# Hifi_Nutube_DAC.net
KiCad netlist of a schematic drawn in EAGLE
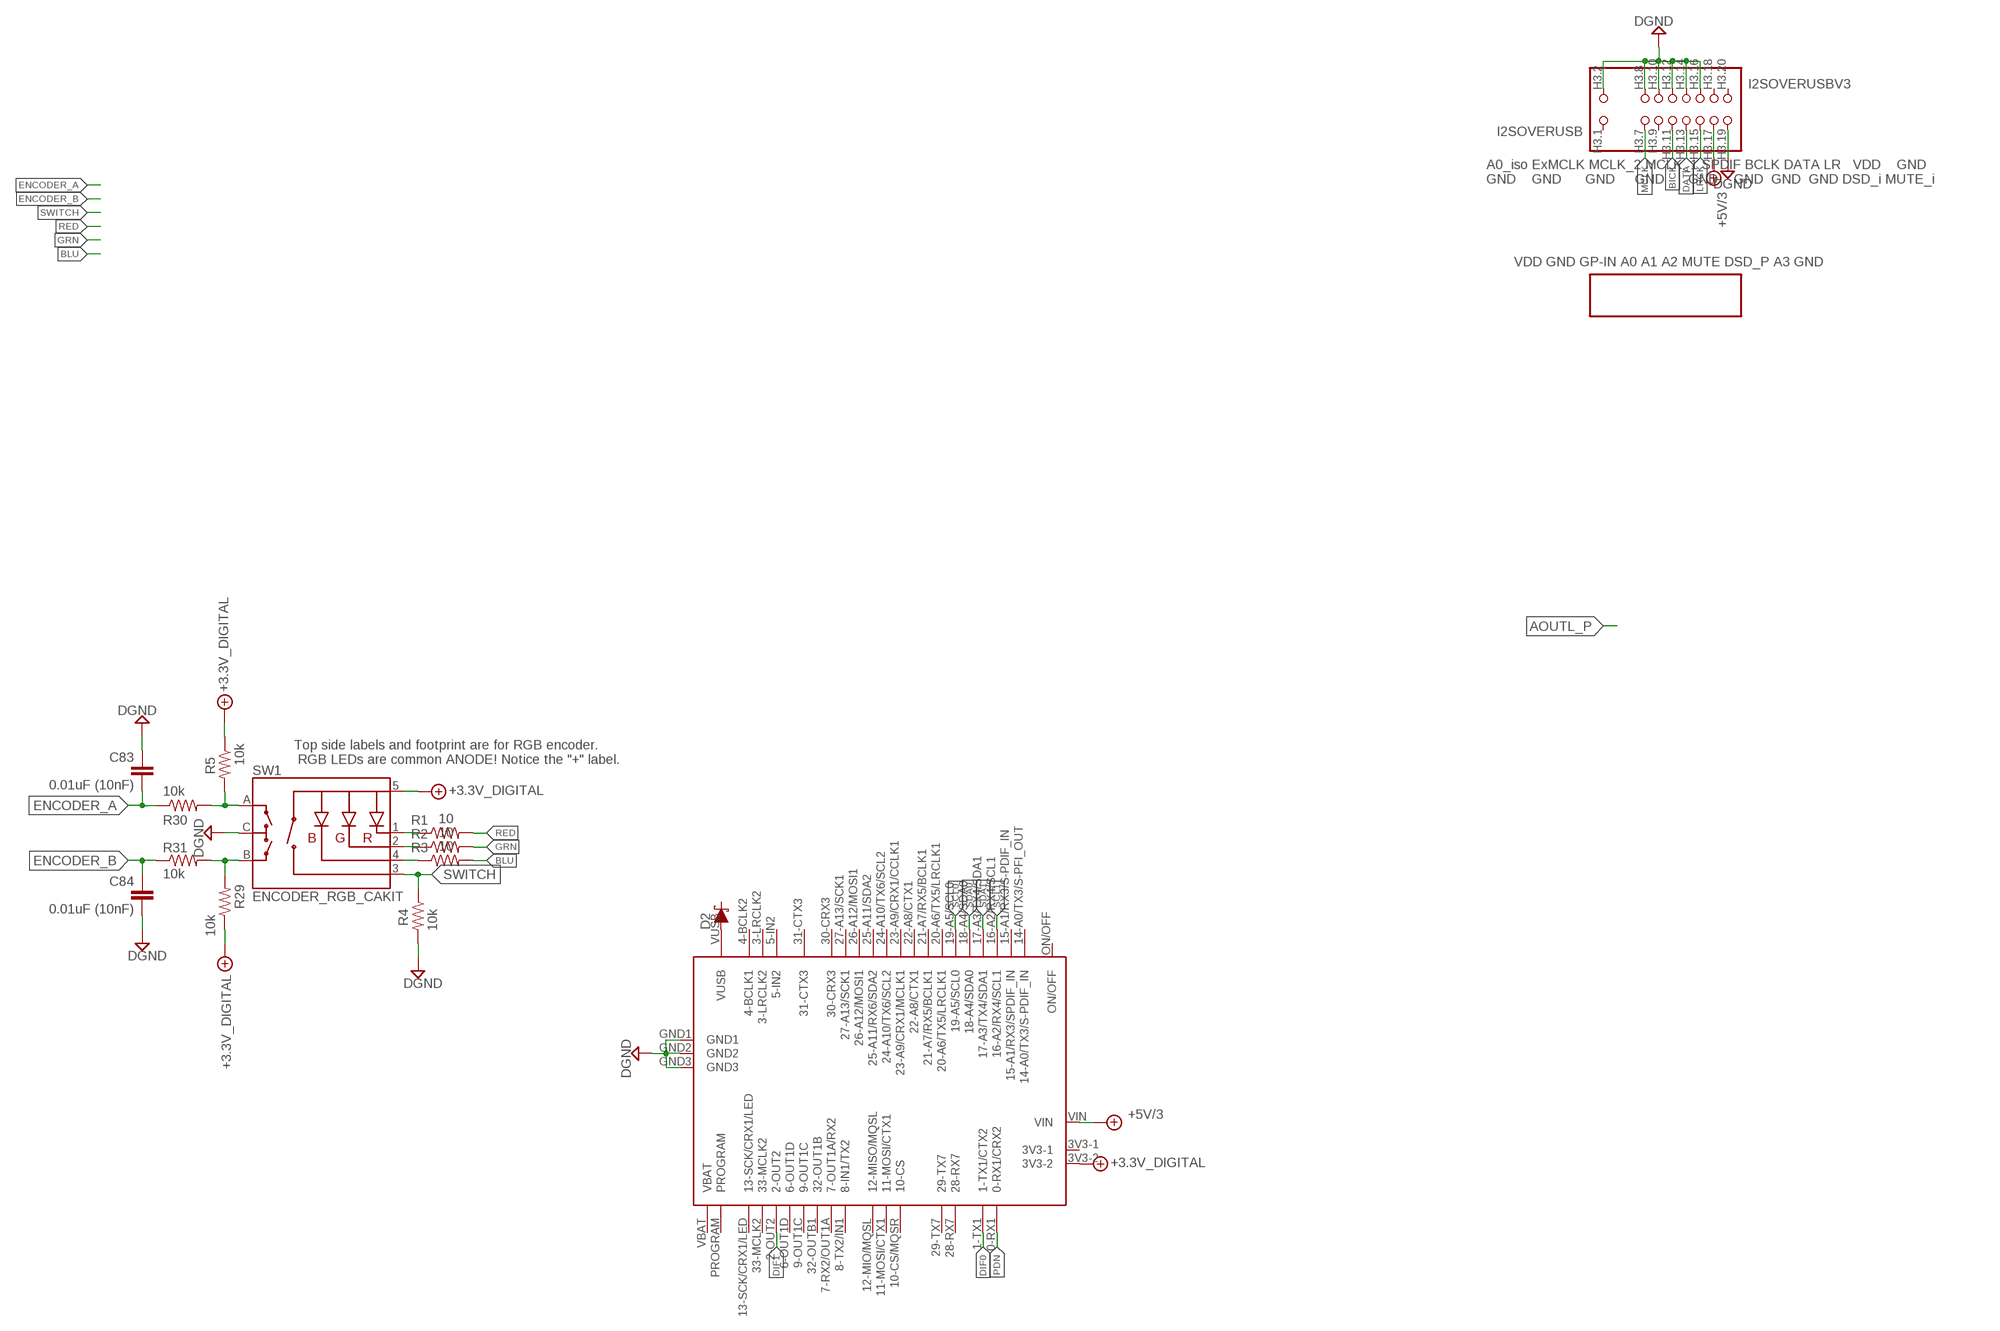
[diagram p0: schematic, sheet 1]

(export (version "E")
  (design (tool "Eeschema 10.0.6"))
  (components
    (comp (ref "C83")
      (value "0.01uF (10nF)")
      (footprint "eagle-import:C0603")
      (fields
        (field (name "DISTRIBUTOR_PART_NUMBER") "710-885012206014")
        (field (name "MANUFACTURER_PART_NUMBER") "885012206014")
      )
      (libsource (lib "eagle-import") (part "C__0603885012206014"))
    )
    (comp (ref "C84")
      (value "0.01uF (10nF)")
      (footprint "eagle-import:C0603")
      (fields
        (field (name "DISTRIBUTOR_PART_NUMBER") "710-885012206014")
        (field (name "MANUFACTURER_PART_NUMBER") "885012206014")
      )
      (libsource (lib "eagle-import") (part "C__0603885012206014"))
    )
    (comp (ref "D2")
      (value "SS14-DIODE-SCHOTTKY-SS14")
      (footprint "eagle-import:SMA-DIODE")
      (fields
        (field (name "DISTRIBUTOR_PART_NUMBER") "241-SS14_R1_00001")
        (field (name "MANUFACTURER_PART_NUMBER") "SS14_R1_00001")
      )
      (libsource (lib "eagle-import") (part "SS14-DIODE-SCHOTTKY-SS14"))
    )
    (comp (ref "I2SOVERUSB")
      (value "I2SOVERUSBV3")
      (footprint "eagle-import:I2SOVERUSBV3")
      (libsource (lib "eagle-import") (part "I2SOVERUSBV3"))
    )
    (comp (ref "R1")
      (value "10")
      (footprint "eagle-import:R0603")
      (fields
        (field (name "DISTRIBUTOR_PART_NUMBER") "603-RC0603FR-7W10RL")
        (field (name "MANUFACTURER_PART_NUMBER") "RC0603FR-7W10RL")
      )
      (libsource (lib "eagle-import") (part "R__0603RC0603FR-7W10RL"))
    )
    (comp (ref "R2")
      (value "10")
      (footprint "eagle-import:R0603")
      (fields
        (field (name "DISTRIBUTOR_PART_NUMBER") "603-RC0603FR-7W10RL")
        (field (name "MANUFACTURER_PART_NUMBER") "RC0603FR-7W10RL")
      )
      (libsource (lib "eagle-import") (part "R__0603RC0603FR-7W10RL"))
    )
    (comp (ref "R3")
      (value "10")
      (footprint "eagle-import:R0603")
      (fields
        (field (name "DISTRIBUTOR_PART_NUMBER") "603-RC0603FR-7W10RL")
        (field (name "MANUFACTURER_PART_NUMBER") "RC0603FR-7W10RL")
      )
      (libsource (lib "eagle-import") (part "R__0603RC0603FR-7W10RL"))
    )
    (comp (ref "R4")
      (value "10k")
      (footprint "eagle-import:R0603")
      (fields
        (field (name "DISTRIBUTOR_PART_NUMBER") "652-CMP0603AFX-1002L")
        (field (name "MANUFACTURER_PART_NUMBER") "CMP0603AFX-1002ELF")
      )
      (libsource (lib "eagle-import") (part "R__0603CMP0603AFX-1002ELF"))
    )
    (comp (ref "R5")
      (value "10k")
      (footprint "eagle-import:R0603")
      (fields
        (field (name "DISTRIBUTOR_PART_NUMBER") "652-CMP0603AFX-1002L")
        (field (name "MANUFACTURER_PART_NUMBER") "CMP0603AFX-1002ELF")
      )
      (libsource (lib "eagle-import") (part "R__0603CMP0603AFX-1002ELF"))
    )
    (comp (ref "R29")
      (value "10k")
      (footprint "eagle-import:R0603")
      (fields
        (field (name "DISTRIBUTOR_PART_NUMBER") "652-CMP0603AFX-1002L")
        (field (name "MANUFACTURER_PART_NUMBER") "CMP0603AFX-1002ELF")
      )
      (libsource (lib "eagle-import") (part "R__0603CMP0603AFX-1002ELF"))
    )
    (comp (ref "R30")
      (value "10k")
      (footprint "eagle-import:R0603")
      (fields
        (field (name "DISTRIBUTOR_PART_NUMBER") "652-CMP0603AFX-1002L")
        (field (name "MANUFACTURER_PART_NUMBER") "CMP0603AFX-1002ELF")
      )
      (libsource (lib "eagle-import") (part "R__0603CMP0603AFX-1002ELF"))
    )
    (comp (ref "R31")
      (value "10k")
      (footprint "eagle-import:R0603")
      (fields
        (field (name "DISTRIBUTOR_PART_NUMBER") "652-CMP0603AFX-1002L")
        (field (name "MANUFACTURER_PART_NUMBER") "CMP0603AFX-1002ELF")
      )
      (libsource (lib "eagle-import") (part "R__0603CMP0603AFX-1002ELF"))
    )
    (comp (ref "SW1")
      (value "ENCODER_RGB_CAKIT")
      (footprint "eagle-import:ENCODER_LED_3_KIT")
      (libsource (lib "eagle-import") (part "ENCODER_RGB_CAKIT"))
    )
    (comp (ref "U$4")
      (value "TEENSY40")
      (footprint "eagle-import:TEENSY40")
      (libsource (lib "eagle-import") (part "TEENSY40"))
    )
  )
  (nets
    (net (code "1") (name "+3.3V_DIGITAL") (class "Default")
      (node (ref "R29") (pin "1") (pinfunction "1_1") (pintype "passive"))
      (node (ref "R5") (pin "1") (pinfunction "1_1") (pintype "passive"))
      (node (ref "SW1") (pin "5") (pinfunction "+_5") (pintype "passive"))
      (node (ref "U$4") (pin "3V3-2") (pinfunction "3V3-2_3V3-2") (pintype "bidirectional"))
    )
    (net (code "2") (name "+5V{slash}3") (class "Default")
      (node (ref "I2SOVERUSB") (pin "H3.17") (pinfunction "H3.17_H3.17") (pintype "passive"))
      (node (ref "U$4") (pin "VIN") (pinfunction "VIN_VIN") (pintype "bidirectional"))
    )
    (net (code "4") (name "BICK") (class "Default")
      (node (ref "I2SOVERUSB") (pin "H3.11") (pinfunction "H3.11_H3.11") (pintype "passive"))
    )
    (net (code "5") (name "BLU") (class "Default")
      (node (ref "R3") (pin "2") (pinfunction "2_2") (pintype "passive"))
    )
    (net (code "6") (name "DATA") (class "Default")
      (node (ref "I2SOVERUSB") (pin "H3.13") (pinfunction "H3.13_H3.13") (pintype "passive"))
    )
    (net (code "7") (name "DGND") (class "Default")
      (node (ref "C83") (pin "1") (pinfunction "1_1") (pintype "passive"))
      (node (ref "C84") (pin "2") (pinfunction "2_2") (pintype "passive"))
      (node (ref "I2SOVERUSB") (pin "H3.10") (pinfunction "H3.10_H3.10") (pintype "passive"))
      (node (ref "I2SOVERUSB") (pin "H3.12") (pinfunction "H3.12_H3.12") (pintype "passive"))
      (node (ref "I2SOVERUSB") (pin "H3.14") (pinfunction "H3.14_H3.14") (pintype "passive"))
      (node (ref "I2SOVERUSB") (pin "H3.16") (pinfunction "H3.16_H3.16") (pintype "passive"))
      (node (ref "I2SOVERUSB") (pin "H3.19") (pinfunction "H3.19_H3.19") (pintype "passive"))
      (node (ref "I2SOVERUSB") (pin "H3.2") (pinfunction "H3.2_H3.2") (pintype "passive"))
      (node (ref "I2SOVERUSB") (pin "H3.8") (pinfunction "H3.8_H3.8") (pintype "passive"))
      (node (ref "R4") (pin "2") (pinfunction "2_2") (pintype "passive"))
      (node (ref "SW1") (pin "C") (pinfunction "C_C") (pintype "bidirectional"))
      (node (ref "U$4") (pin "GND1") (pinfunction "GND1_GND1") (pintype "bidirectional"))
      (node (ref "U$4") (pin "GND2") (pinfunction "GND2_GND2") (pintype "bidirectional"))
      (node (ref "U$4") (pin "GND3") (pinfunction "GND3_GND3") (pintype "bidirectional"))
    )
    (net (code "8") (name "DIF0") (class "Default")
      (node (ref "U$4") (pin "1-TX1") (pinfunction "1-TX1/CTX2_1-TX1") (pintype "bidirectional"))
    )
    (net (code "9") (name "DIF1") (class "Default")
      (node (ref "U$4") (pin "2-OUT2") (pinfunction "2-OUT2_2-OUT2") (pintype "bidirectional"))
    )
    (net (code "10") (name "ENCODER_A") (class "Default")
      (node (ref "C83") (pin "2") (pinfunction "2_2") (pintype "passive"))
      (node (ref "R30") (pin "1") (pinfunction "1_1") (pintype "passive"))
    )
    (net (code "11") (name "ENCODER_B") (class "Default")
      (node (ref "C84") (pin "1") (pinfunction "1_1") (pintype "passive"))
      (node (ref "R31") (pin "1") (pinfunction "1_1") (pintype "passive"))
    )
    (net (code "12") (name "GRN") (class "Default")
      (node (ref "R2") (pin "2") (pinfunction "2_2") (pintype "passive"))
    )
    (net (code "13") (name "LRCK") (class "Default")
      (node (ref "I2SOVERUSB") (pin "H3.15") (pinfunction "H3.15_H3.15") (pintype "passive"))
    )
    (net (code "14") (name "MCLK") (class "Default")
      (node (ref "I2SOVERUSB") (pin "H3.7") (pinfunction "H3.7_H3.7") (pintype "passive"))
    )
    (net (code "15") (name "Net-(D2-PadA)") (class "Default")
      (node (ref "D2") (pin "A") (pinfunction "A_A") (pintype "passive"))
      (node (ref "U$4") (pin "VUSB") (pinfunction "VUSB_VUSB") (pintype "bidirectional"))
    )
    (net (code "16") (name "Net-(R29-Pad2)") (class "Default")
      (node (ref "R29") (pin "2") (pinfunction "2_2") (pintype "passive"))
      (node (ref "R31") (pin "2") (pinfunction "2_2") (pintype "passive"))
      (node (ref "SW1") (pin "B") (pinfunction "B_B") (pintype "bidirectional"))
    )
    (net (code "17") (name "Net-(R30-Pad2)") (class "Default")
      (node (ref "R30") (pin "2") (pinfunction "2_2") (pintype "passive"))
      (node (ref "R5") (pin "2") (pinfunction "2_2") (pintype "passive"))
      (node (ref "SW1") (pin "A") (pinfunction "A_A") (pintype "bidirectional"))
    )
    (net (code "18") (name "Net-(SW1--B)") (class "Default")
      (node (ref "R3") (pin "1") (pinfunction "1_1") (pintype "passive"))
      (node (ref "SW1") (pin "4") (pinfunction "-B_4") (pintype "passive"))
    )
    (net (code "19") (name "Net-(SW1--G)") (class "Default")
      (node (ref "R2") (pin "1") (pinfunction "1_1") (pintype "passive"))
      (node (ref "SW1") (pin "2") (pinfunction "-G_2") (pintype "passive"))
    )
    (net (code "20") (name "Net-(SW1--R)") (class "Default")
      (node (ref "R1") (pin "1") (pinfunction "1_1") (pintype "passive"))
      (node (ref "SW1") (pin "1") (pinfunction "-R_1") (pintype "passive"))
    )
    (net (code "21") (name "PDN") (class "Default")
      (node (ref "U$4") (pin "0-RX1") (pinfunction "0-RX1/CRX2_0-RX1") (pintype "bidirectional"))
    )
    (net (code "22") (name "RED") (class "Default")
      (node (ref "R1") (pin "2") (pinfunction "2_2") (pintype "passive"))
    )
    (net (code "23") (name "SCL0") (class "Default")
      (node (ref "U$4") (pin "19-A5/SCL0") (pinfunction "19-A5/SCL0_19-A5/SCL0") (pintype "bidirectional"))
    )
    (net (code "24") (name "SCL1") (class "Default")
      (node (ref "U$4") (pin "16-A2/RX4/SCL1") (pinfunction "16-A2/RX4/SCL1_16-A2/RX4/SCL1") (pintype "bidirectional"))
    )
    (net (code "25") (name "SDA0") (class "Default")
      (node (ref "U$4") (pin "18-A4/SDA0") (pinfunction "18-A4/SDA0_18-A4/SDA0") (pintype "bidirectional"))
    )
    (net (code "26") (name "SDA1") (class "Default")
      (node (ref "U$4") (pin "17-A3/TX4/SDA1") (pinfunction "17-A3/TX4/SDA1_17-A3/TX4/SDA1") (pintype "bidirectional"))
    )
    (net (code "27") (name "SWITCH") (class "Default")
      (node (ref "R4") (pin "1") (pinfunction "1_1") (pintype "passive"))
      (node (ref "SW1") (pin "3") (pinfunction "SW_3") (pintype "passive"))
    )
    (net (code "28") (name "unconnected-(D2-PadC)") (class "Default")
      (node (ref "D2") (pin "C") (pinfunction "C_C") (pintype "passive"))
    )
    (net (code "29") (name "unconnected-(I2SOVERUSB-PadH3.1)") (class "Default")
      (node (ref "I2SOVERUSB") (pin "H3.1") (pinfunction "H3.1_H3.1") (pintype "passive"))
    )
    (net (code "30") (name "unconnected-(I2SOVERUSB-PadH3.9)") (class "Default")
      (node (ref "I2SOVERUSB") (pin "H3.9") (pinfunction "H3.9_H3.9") (pintype "passive"))
    )
    (net (code "31") (name "unconnected-(I2SOVERUSB-PadH3.18)") (class "Default")
      (node (ref "I2SOVERUSB") (pin "H3.18") (pinfunction "H3.18_H3.18") (pintype "passive"))
    )
    (net (code "32") (name "unconnected-(I2SOVERUSB-PadH3.20)") (class "Default")
      (node (ref "I2SOVERUSB") (pin "H3.20") (pinfunction "H3.20_H3.20") (pintype "passive"))
    )
    (net (code "33") (name "unconnected-(U$4-4-BCLK1-Pad4-BCLK2)") (class "Default")
      (node (ref "U$4") (pin "4-BCLK2") (pinfunction "4-BCLK1_4-BCLK2") (pintype "bidirectional"))
    )
    (net (code "34") (name "unconnected-(U$4-7-OUT1A{slash}RX2-Pad7-RX2{slash}OUT1A)") (class "Default")
      (node (ref "U$4") (pin "7-RX2/OUT1A") (pinfunction "7-OUT1A/RX2_7-RX2/OUT1A") (pintype "bidirectional"))
    )
    (net (code "35") (name "unconnected-(U$4-8-IN1{slash}TX2-Pad8-TX2{slash}IN1)") (class "Default")
      (node (ref "U$4") (pin "8-TX2/IN1") (pinfunction "8-IN1/TX2_8-TX2/IN1") (pintype "bidirectional"))
    )
    (net (code "36") (name "unconnected-(U$4-10-CS-Pad10-CS{slash}MQSR)") (class "Default")
      (node (ref "U$4") (pin "10-CS/MQSR") (pinfunction "10-CS_10-CS/MQSR") (pintype "bidirectional"))
    )
    (net (code "37") (name "unconnected-(U$4-12-MISO{slash}MQSL-Pad12-MIO{slash}MQSL)") (class "Default")
      (node (ref "U$4") (pin "12-MIO/MQSL") (pinfunction "12-MISO/MQSL_12-MIO/MQSL") (pintype "bidirectional"))
    )
    (net (code "38") (name "unconnected-(U$4-14-A0{slash}TX3{slash}S-PDIF_IN-Pad14-A0{slash}TX3{slash}S-PFI_OUT)") (class "Default")
      (node (ref "U$4") (pin "14-A0/TX3/S-PFI_OUT") (pinfunction "14-A0/TX3/S-PDIF_IN_14-A0/TX3/S-PFI_OUT") (pintype "bidirectional"))
    )
    (net (code "39") (name "unconnected-(U$4-15-A1{slash}RX3{slash}SPDIF_IN-Pad15-A1{slash}RX3{slash}S-PDIF_IN)") (class "Default")
      (node (ref "U$4") (pin "15-A1/RX3/S-PDIF_IN") (pinfunction "15-A1/RX3/SPDIF_IN_15-A1/RX3/S-PDIF_IN") (pintype "bidirectional"))
    )
    (net (code "40") (name "unconnected-(U$4-23-A9{slash}CRX1{slash}MCLK1-Pad23-A9{slash}CRX1{slash}CCLK1)") (class "Default")
      (node (ref "U$4") (pin "23-A9/CRX1/CCLK1") (pinfunction "23-A9/CRX1/MCLK1_23-A9/CRX1/CCLK1") (pintype "bidirectional"))
    )
    (net (code "41") (name "unconnected-(U$4-25-A11{slash}RX6{slash}SDA2-Pad25-A11{slash}SDA2)") (class "Default")
      (node (ref "U$4") (pin "25-A11/SDA2") (pinfunction "25-A11/RX6/SDA2_25-A11/SDA2") (pintype "bidirectional"))
    )
    (net (code "42") (name "unconnected-(U$4-32-OUT1B-Pad32-OUTB1)") (class "Default")
      (node (ref "U$4") (pin "32-OUTB1") (pinfunction "32-OUT1B_32-OUTB1") (pintype "bidirectional"))
    )
    (net (code "43") (name "unconnected-(U$4-Pad3-LRCLK2)") (class "Default")
      (node (ref "U$4") (pin "3-LRCLK2") (pinfunction "3-LRCLK2_3-LRCLK2") (pintype "bidirectional"))
    )
    (net (code "44") (name "unconnected-(U$4-Pad3V3-1)") (class "Default")
      (node (ref "U$4") (pin "3V3-1") (pinfunction "3V3-1_3V3-1") (pintype "bidirectional"))
    )
    (net (code "45") (name "unconnected-(U$4-Pad5-IN2)") (class "Default")
      (node (ref "U$4") (pin "5-IN2") (pinfunction "5-IN2_5-IN2") (pintype "bidirectional"))
    )
    (net (code "46") (name "unconnected-(U$4-Pad6-OUT1D)") (class "Default")
      (node (ref "U$4") (pin "6-OUT1D") (pinfunction "6-OUT1D_6-OUT1D") (pintype "bidirectional"))
    )
    (net (code "47") (name "unconnected-(U$4-Pad9-OUT1C)") (class "Default")
      (node (ref "U$4") (pin "9-OUT1C") (pinfunction "9-OUT1C_9-OUT1C") (pintype "bidirectional"))
    )
    (net (code "48") (name "unconnected-(U$4-Pad11-MOSI{slash}CTX1)") (class "Default")
      (node (ref "U$4") (pin "11-MOSI/CTX1") (pinfunction "11-MOSI/CTX1_11-MOSI/CTX1") (pintype "bidirectional"))
    )
    (net (code "49") (name "unconnected-(U$4-Pad13-SCK{slash}CRX1{slash}LED)") (class "Default")
      (node (ref "U$4") (pin "13-SCK/CRX1/LED") (pinfunction "13-SCK/CRX1/LED_13-SCK/CRX1/LED") (pintype "bidirectional"))
    )
    (net (code "50") (name "unconnected-(U$4-Pad20-A6{slash}TX5{slash}LRCLK1)") (class "Default")
      (node (ref "U$4") (pin "20-A6/TX5/LRCLK1") (pinfunction "20-A6/TX5/LRCLK1_20-A6/TX5/LRCLK1") (pintype "bidirectional"))
    )
    (net (code "51") (name "unconnected-(U$4-Pad21-A7{slash}RX5{slash}BCLK1)") (class "Default")
      (node (ref "U$4") (pin "21-A7/RX5/BCLK1") (pinfunction "21-A7/RX5/BCLK1_21-A7/RX5/BCLK1") (pintype "bidirectional"))
    )
    (net (code "52") (name "unconnected-(U$4-Pad22-A8{slash}CTX1)") (class "Default")
      (node (ref "U$4") (pin "22-A8/CTX1") (pinfunction "22-A8/CTX1_22-A8/CTX1") (pintype "bidirectional"))
    )
    (net (code "53") (name "unconnected-(U$4-Pad24-A10{slash}TX6{slash}SCL2)") (class "Default")
      (node (ref "U$4") (pin "24-A10/TX6/SCL2") (pinfunction "24-A10/TX6/SCL2_24-A10/TX6/SCL2") (pintype "bidirectional"))
    )
    (net (code "54") (name "unconnected-(U$4-Pad26-A12{slash}MOSI1)") (class "Default")
      (node (ref "U$4") (pin "26-A12/MOSI1") (pinfunction "26-A12/MOSI1_26-A12/MOSI1") (pintype "bidirectional"))
    )
    (net (code "55") (name "unconnected-(U$4-Pad27-A13{slash}SCK1)") (class "Default")
      (node (ref "U$4") (pin "27-A13/SCK1") (pinfunction "27-A13/SCK1_27-A13/SCK1") (pintype "bidirectional"))
    )
    (net (code "56") (name "unconnected-(U$4-Pad28-RX7)") (class "Default")
      (node (ref "U$4") (pin "28-RX7") (pinfunction "28-RX7_28-RX7") (pintype "bidirectional"))
    )
    (net (code "57") (name "unconnected-(U$4-Pad29-TX7)") (class "Default")
      (node (ref "U$4") (pin "29-TX7") (pinfunction "29-TX7_29-TX7") (pintype "bidirectional"))
    )
    (net (code "58") (name "unconnected-(U$4-Pad30-CRX3)") (class "Default")
      (node (ref "U$4") (pin "30-CRX3") (pinfunction "30-CRX3_30-CRX3") (pintype "bidirectional"))
    )
    (net (code "59") (name "unconnected-(U$4-Pad31-CTX3)") (class "Default")
      (node (ref "U$4") (pin "31-CTX3") (pinfunction "31-CTX3_31-CTX3") (pintype "bidirectional"))
    )
    (net (code "60") (name "unconnected-(U$4-Pad33-MCLK2)") (class "Default")
      (node (ref "U$4") (pin "33-MCLK2") (pinfunction "33-MCLK2_33-MCLK2") (pintype "bidirectional"))
    )
    (net (code "61") (name "unconnected-(U$4-PadON{slash}OFF)") (class "Default")
      (node (ref "U$4") (pin "ON/OFF") (pinfunction "ON/OFF_ON/OFF") (pintype "bidirectional"))
    )
    (net (code "62") (name "unconnected-(U$4-PadPROGRAM)") (class "Default")
      (node (ref "U$4") (pin "PROGRAM") (pinfunction "PROGRAM_PROGRAM") (pintype "bidirectional"))
    )
    (net (code "63") (name "unconnected-(U$4-PadVBAT)") (class "Default")
      (node (ref "U$4") (pin "VBAT") (pinfunction "VBAT_VBAT") (pintype "bidirectional"))
    )
  )
)
